# ESPFA.net
KiCad netlist of a schematic drawn in EAGLE
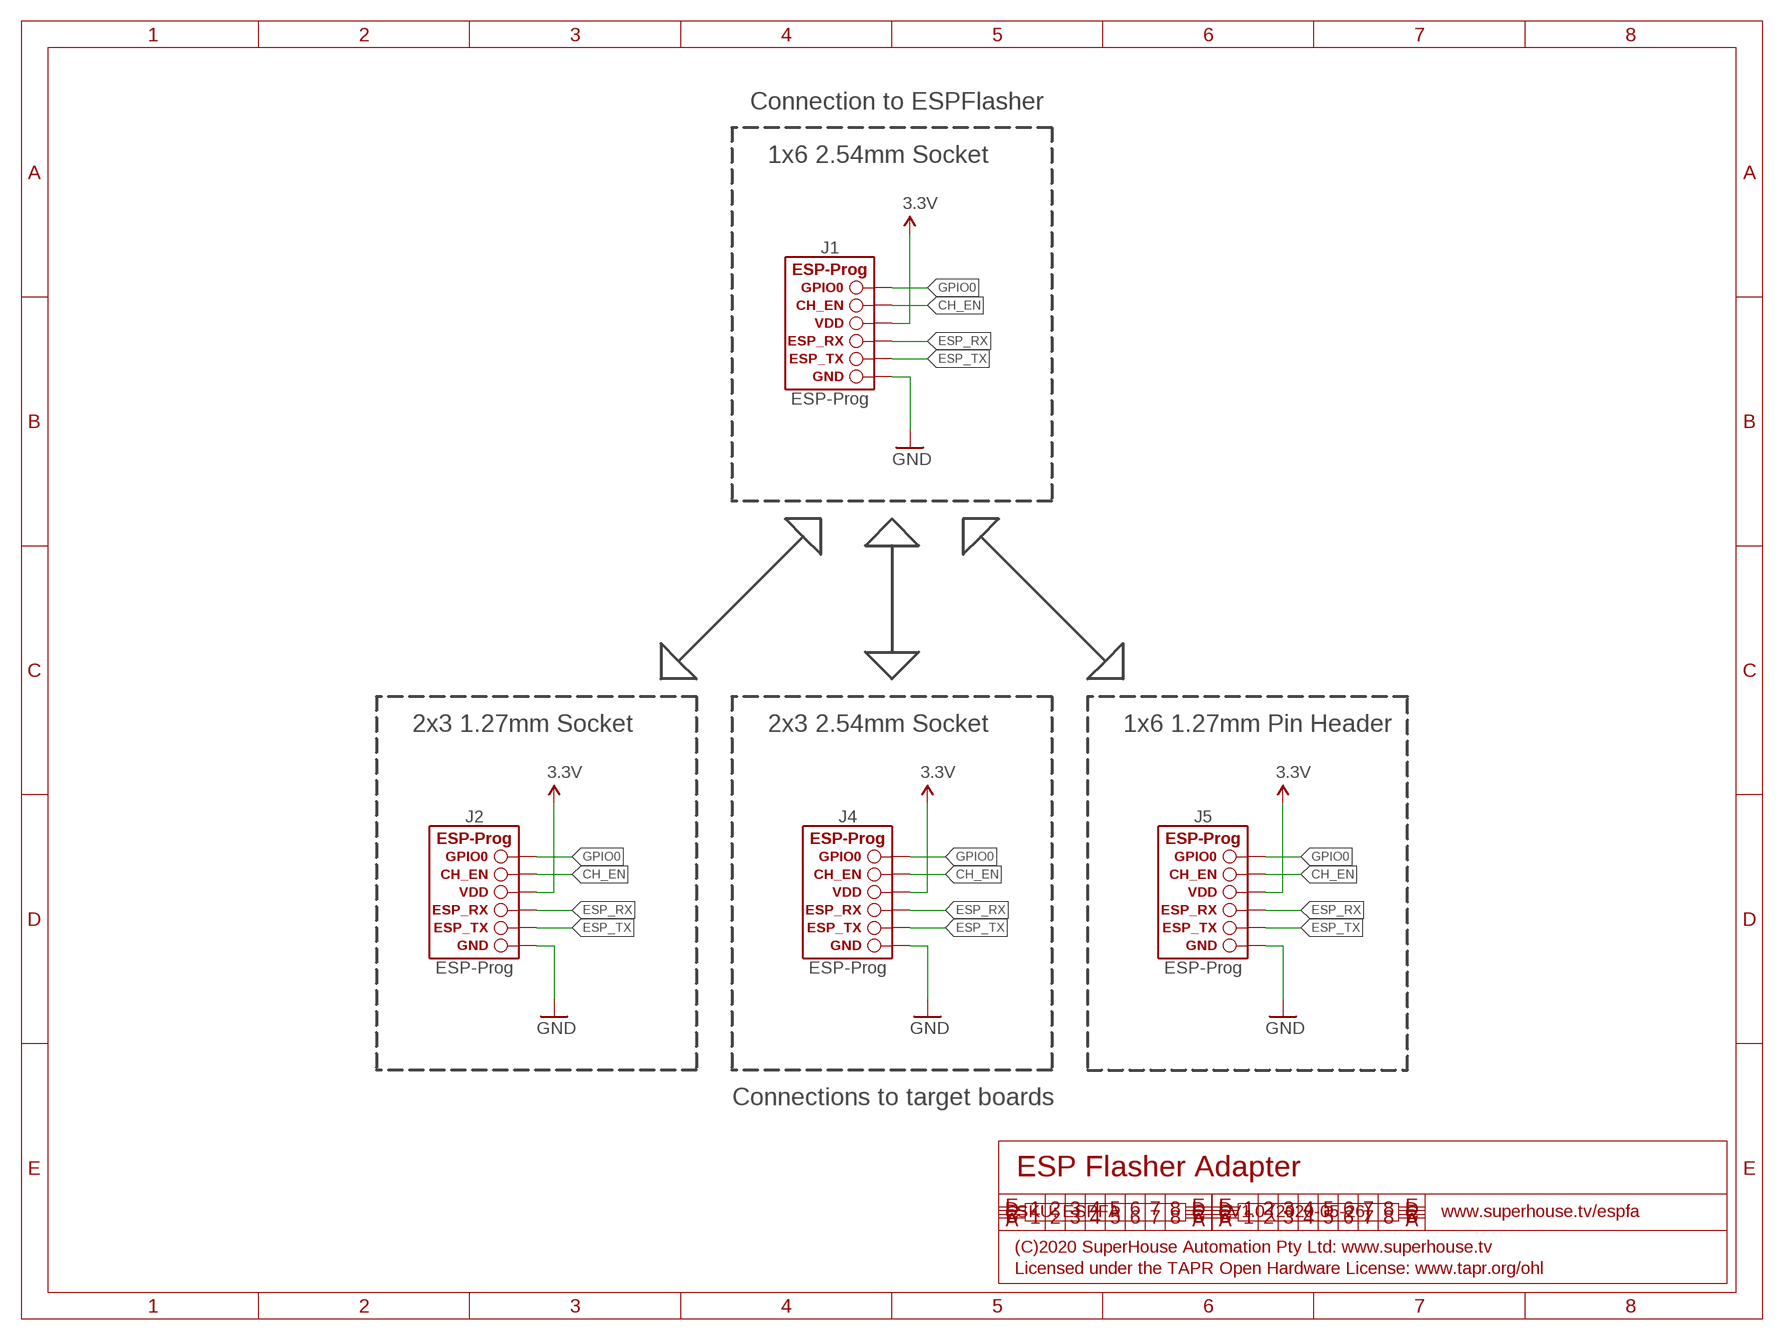
[diagram p0: schematic, sheet 1]

(export (version "E")
  (design (tool "Eeschema 10.0.6"))
  (components
    (comp (ref "J1")
      (value "ESP-PROG-1X6-2.54-SOCKET-RA")
      (footprint "eagle-import:1X6-2.54-SOCKET-RA")
      (libsource (lib "eagle-import") (part "ESP-PROG-1X6-2.54-SOCKET-RA"))
    )
    (comp (ref "J2")
      (value "ESP-PROG-2X3-1.27-SHROUDED")
      (footprint "eagle-import:2X3-1.27-SHROUDED")
      (libsource (lib "eagle-import") (part "ESP-PROG-2X3-1.27-SHROUDED"))
    )
    (comp (ref "J4")
      (value "ESP-PROG-2X3-2.54-SHROUDED")
      (footprint "eagle-import:2X3-2.54-SHROUDED")
      (libsource (lib "eagle-import") (part "ESP-PROG-2X3-2.54-SHROUDED"))
    )
    (comp (ref "J5")
      (value "ESP-PROG-1X6-1.27-PINS-RA")
      (footprint "eagle-import:1X6-1.27-PINS-RA")
      (libsource (lib "eagle-import") (part "ESP-PROG-1X6-1.27-PINS-RA"))
    )
  )
  (nets
    (net (code "1") (name "3.3V") (class "Default")
      (node (ref "J1") (pin "4") (pinfunction "VDD_4") (pintype "passive"))
      (node (ref "J2") (pin "2") (pinfunction "VDD_2") (pintype "passive"))
      (node (ref "J4") (pin "2") (pinfunction "VDD_2") (pintype "passive"))
      (node (ref "J5") (pin "4") (pinfunction "VDD_4") (pintype "passive"))
    )
    (net (code "2") (name "CH_EN") (class "Default")
      (node (ref "J1") (pin "5") (pinfunction "CH_EN_5") (pintype "passive"))
      (node (ref "J2") (pin "1") (pinfunction "CH_EN_1") (pintype "passive"))
      (node (ref "J4") (pin "1") (pinfunction "CH_EN_1") (pintype "passive"))
      (node (ref "J5") (pin "5") (pinfunction "CH_EN_5") (pintype "passive"))
    )
    (net (code "3") (name "ESP_RX") (class "Default")
      (node (ref "J1") (pin "3") (pinfunction "ESP_RX_3") (pintype "passive"))
      (node (ref "J2") (pin "5") (pinfunction "ESP_RX_5") (pintype "passive"))
      (node (ref "J4") (pin "5") (pinfunction "ESP_RX_5") (pintype "passive"))
      (node (ref "J5") (pin "3") (pinfunction "ESP_RX_3") (pintype "passive"))
    )
    (net (code "4") (name "ESP_TX") (class "Default")
      (node (ref "J1") (pin "2") (pinfunction "ESP_TX_2") (pintype "passive"))
      (node (ref "J2") (pin "3") (pinfunction "ESP_TX_3") (pintype "passive"))
      (node (ref "J4") (pin "3") (pinfunction "ESP_TX_3") (pintype "passive"))
      (node (ref "J5") (pin "2") (pinfunction "ESP_TX_2") (pintype "passive"))
    )
    (net (code "5") (name "GND") (class "Default")
      (node (ref "J1") (pin "1") (pinfunction "GND_1") (pintype "passive"))
      (node (ref "J2") (pin "4") (pinfunction "GND_4") (pintype "passive"))
      (node (ref "J4") (pin "4") (pinfunction "GND_4") (pintype "passive"))
      (node (ref "J5") (pin "1") (pinfunction "GND_1") (pintype "passive"))
    )
    (net (code "6") (name "GPIO0") (class "Default")
      (node (ref "J1") (pin "6") (pinfunction "GPIO0_6") (pintype "passive"))
      (node (ref "J2") (pin "6") (pinfunction "GPIO0_6") (pintype "passive"))
      (node (ref "J4") (pin "6") (pinfunction "GPIO0_6") (pintype "passive"))
      (node (ref "J5") (pin "6") (pinfunction "GPIO0_6") (pintype "passive"))
    )
  )
)
